# GPSClock.net
KiCad netlist of a schematic drawn in EAGLE
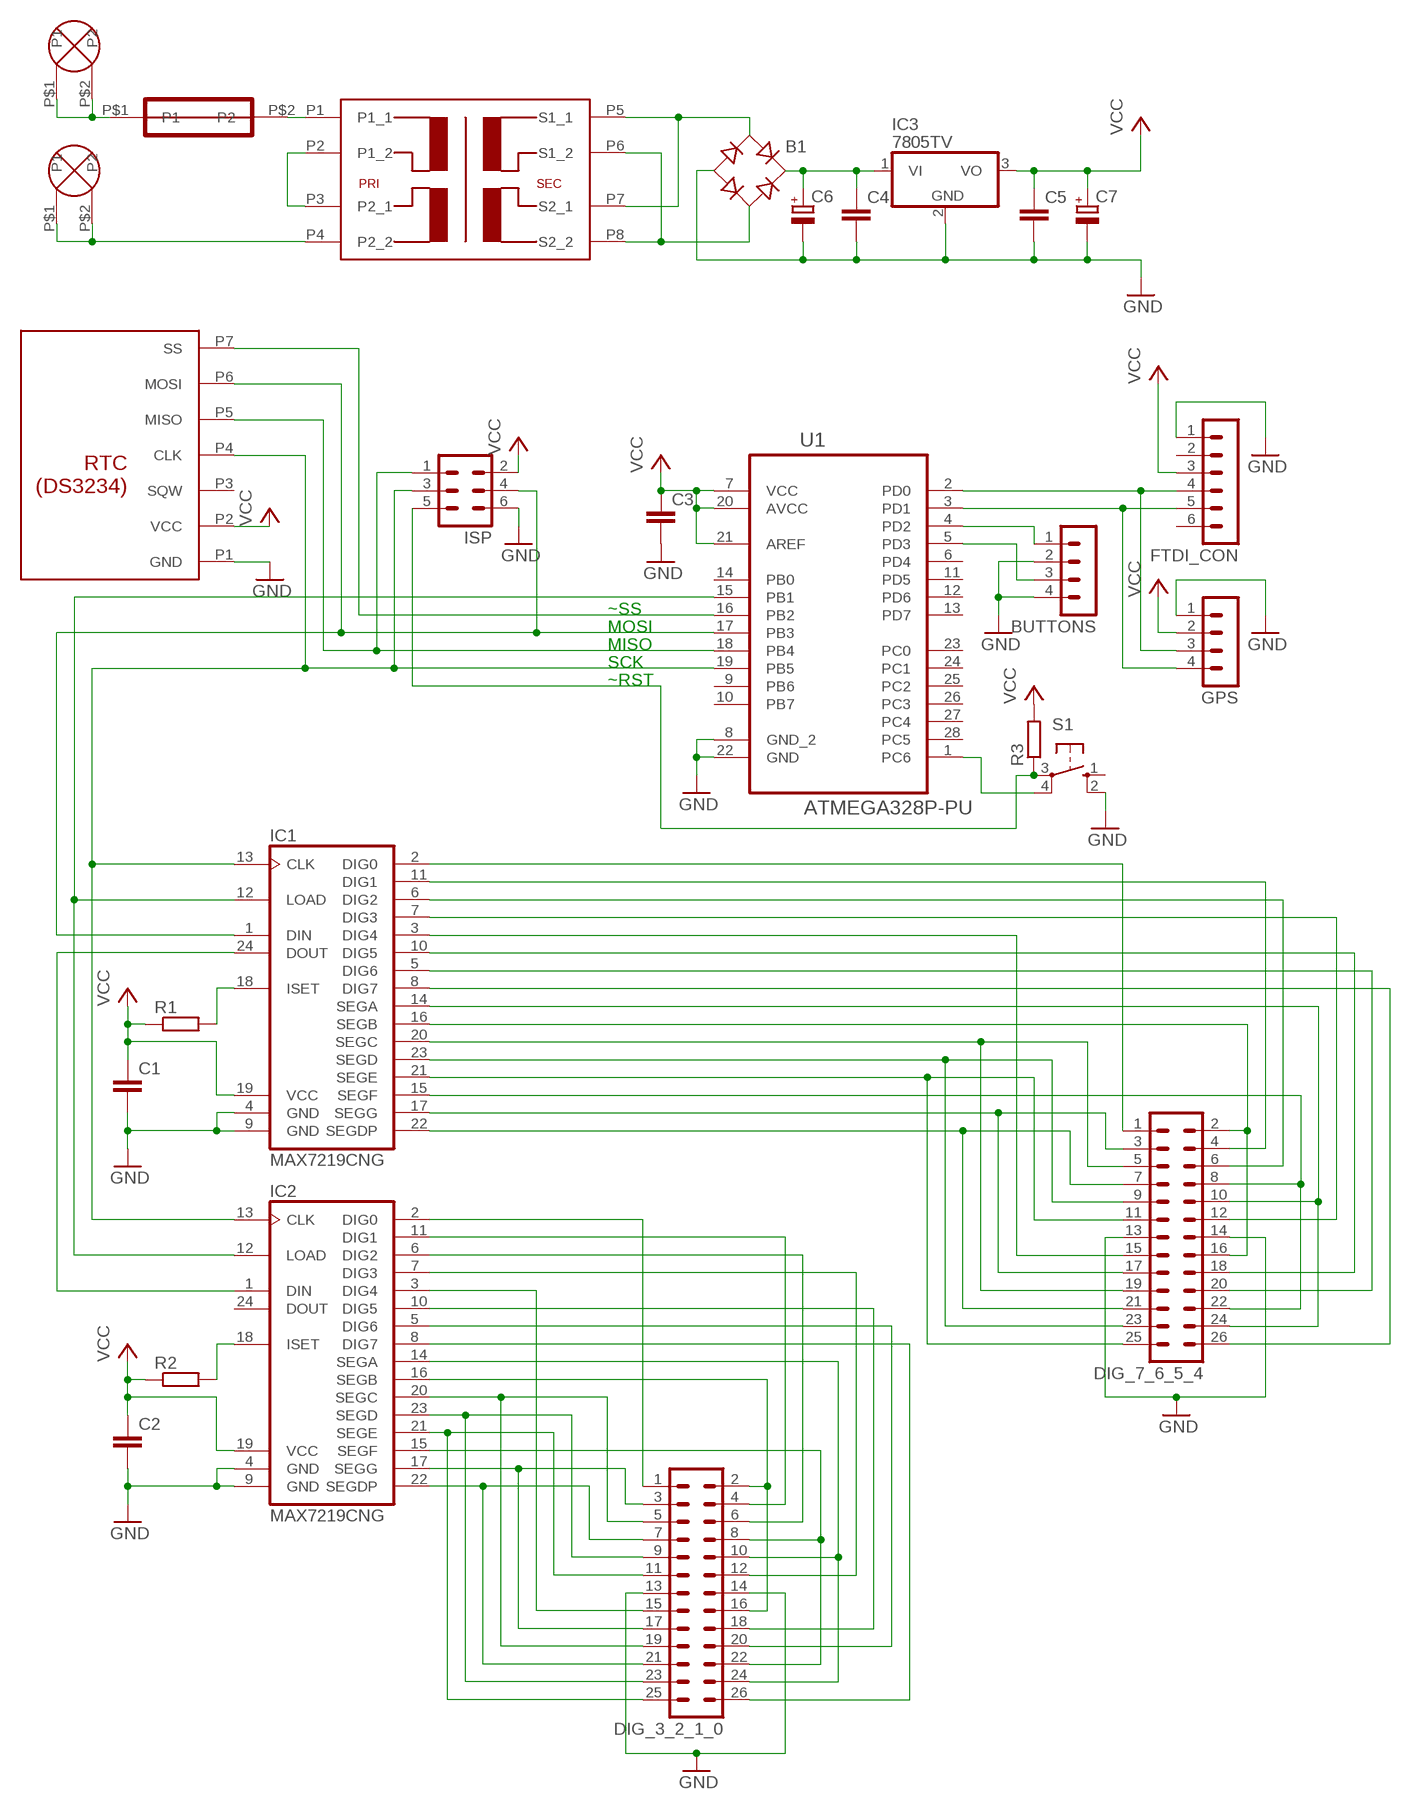
[diagram p0: schematic, sheet 1]

(export (version "E")
  (design (tool "Eeschema 10.0.6"))
  (components
    (comp (ref "B1")
      (value "RB1A")
      (footprint "eagle-import:RB1A")
      (libsource (lib "eagle-import") (part "RB1A"))
    )
    (comp (ref "BUTTONS")
      (value "MA04-1")
      (footprint "eagle-import:MA04-1")
      (libsource (lib "eagle-import") (part "MA04-1"))
    )
    (comp (ref "C1")
      (value "C-EU050-025X075")
      (footprint "eagle-import:C050-025X075")
      (libsource (lib "eagle-import") (part "C-EU050-025X075"))
    )
    (comp (ref "C2")
      (value "C-EU050-025X075")
      (footprint "eagle-import:C050-025X075")
      (libsource (lib "eagle-import") (part "C-EU050-025X075"))
    )
    (comp (ref "C3")
      (value "C-EU050-025X075")
      (footprint "eagle-import:C050-025X075")
      (libsource (lib "eagle-import") (part "C-EU050-025X075"))
    )
    (comp (ref "C4")
      (value "C-EU050-025X075")
      (footprint "eagle-import:C050-025X075")
      (libsource (lib "eagle-import") (part "C-EU050-025X075"))
    )
    (comp (ref "C5")
      (value "C-EU050-025X075")
      (footprint "eagle-import:C050-025X075")
      (libsource (lib "eagle-import") (part "C-EU050-025X075"))
    )
    (comp (ref "C6")
      (value "CPOL-EUE5-13")
      (footprint "eagle-import:E5-13")
      (libsource (lib "eagle-import") (part "CPOL-EUE5-13"))
    )
    (comp (ref "C7")
      (value "CPOL-EUE5-10.5")
      (footprint "eagle-import:E5-10,5")
      (libsource (lib "eagle-import") (part "CPOL-EUE5-10.5"))
    )
    (comp (ref "DIG_3_2_1_0")
      (value "ML26")
      (footprint "eagle-import:ML26")
      (libsource (lib "eagle-import") (part "ML26"))
    )
    (comp (ref "DIG_7_6_5_4")
      (value "ML26")
      (footprint "eagle-import:ML26")
      (libsource (lib "eagle-import") (part "ML26"))
    )
    (comp (ref "FTDI_CON")
      (value "MA06-1")
      (footprint "eagle-import:MA06-1")
      (libsource (lib "eagle-import") (part "MA06-1"))
    )
    (comp (ref "GPS")
      (value "MA04-1")
      (footprint "eagle-import:MA04-1")
      (libsource (lib "eagle-import") (part "MA04-1"))
    )
    (comp (ref "IC1")
      (value "MAX7219CNG")
      (footprint "eagle-import:DIL24-3")
      (fields (field (name "MF") "MAXIM"))
      (libsource (lib "eagle-import") (part "MAX7219CNG"))
    )
    (comp (ref "IC2")
      (value "MAX7219CNG")
      (footprint "eagle-import:DIL24-3")
      (fields (field (name "MF") "MAXIM"))
      (libsource (lib "eagle-import") (part "MAX7219CNG"))
    )
    (comp (ref "IC3")
      (value "7805TV")
      (footprint "eagle-import:TO220V")
      (libsource (lib "eagle-import") (part "78TV05"))
    )
    (comp (ref "ISP")
      (value "ML6")
      (footprint "eagle-import:ML6")
      (libsource (lib "eagle-import") (part "ML6"))
    )
    (comp (ref "R1")
      (value "R-EU_0207/10")
      (footprint "eagle-import:0207_10")
      (libsource (lib "eagle-import") (part "R-EU_0207/10"))
    )
    (comp (ref "R2")
      (value "R-EU_0207/10")
      (footprint "eagle-import:0207_10")
      (libsource (lib "eagle-import") (part "R-EU_0207/10"))
    )
    (comp (ref "R3")
      (value "R-EU_0207/10")
      (footprint "eagle-import:0207_10")
      (libsource (lib "eagle-import") (part "R-EU_0207/10"))
    )
    (comp (ref "S1")
      (value "10-XX")
      (footprint "eagle-import:B3F-10XX")
      (fields (field (name "MPN") "B3F-1000"))
      (libsource (lib "eagle-import") (part "10-XX"))
    )
    (comp (ref "U$1")
      (value "TRAFO_M4312")
      (footprint "eagle-import:TRAFO_M4312")
      (libsource (lib "eagle-import") (part "TRAFO_M4312"))
    )
    (comp (ref "U$2")
      (value "SPADE_PCB")
      (footprint "eagle-import:SPADE_PCB")
      (libsource (lib "eagle-import") (part "SPADE_PCB"))
    )
    (comp (ref "U$3")
      (value "SPADE_PCB")
      (footprint "eagle-import:SPADE_PCB")
      (libsource (lib "eagle-import") (part "SPADE_PCB"))
    )
    (comp (ref "U$4")
      (value "FUSE_HOLDER")
      (footprint "eagle-import:FUSE_HOLDER")
      (libsource (lib "eagle-import") (part "FUSE_HOLDER"))
    )
    (comp (ref "U$5")
      (value "RTC")
      (footprint "eagle-import:RTC")
      (libsource (lib "eagle-import") (part "RTC"))
    )
    (comp (ref "U1")
      (value "ATMEGA328P-PU")
      (footprint "eagle-import:DIP254P762X457-28")
      (libsource (lib "eagle-import") (part "ATMEGA328P-PU"))
    )
  )
  (nets
    (net (code "1") (name "GND") (class "Default")
      (node (ref "B1") (pin "-") (pinfunction "-_-") (pintype "passive"))
      (node (ref "BUTTONS") (pin "2") (pinfunction "2_2") (pintype "passive"))
      (node (ref "BUTTONS") (pin "4") (pinfunction "4_4") (pintype "passive"))
      (node (ref "C1") (pin "2") (pinfunction "2_2") (pintype "passive"))
      (node (ref "C2") (pin "2") (pinfunction "2_2") (pintype "passive"))
      (node (ref "C3") (pin "2") (pinfunction "2_2") (pintype "passive"))
      (node (ref "C4") (pin "2") (pinfunction "2_2") (pintype "passive"))
      (node (ref "C5") (pin "2") (pinfunction "2_2") (pintype "passive"))
      (node (ref "C6") (pin "-") (pinfunction "-_-") (pintype "passive"))
      (node (ref "C7") (pin "-") (pinfunction "-_-") (pintype "passive"))
      (node (ref "DIG_3_2_1_0") (pin "13") (pinfunction "13_13") (pintype "passive"))
      (node (ref "DIG_3_2_1_0") (pin "14") (pinfunction "14_14") (pintype "passive"))
      (node (ref "DIG_7_6_5_4") (pin "13") (pinfunction "13_13") (pintype "passive"))
      (node (ref "DIG_7_6_5_4") (pin "14") (pinfunction "14_14") (pintype "passive"))
      (node (ref "FTDI_CON") (pin "1") (pinfunction "1_1") (pintype "passive"))
      (node (ref "GPS") (pin "1") (pinfunction "1_1") (pintype "passive"))
      (node (ref "IC1") (pin "4") (pinfunction "GND_4") (pintype "power_in"))
      (node (ref "IC1") (pin "9") (pinfunction "GND_9") (pintype "power_in"))
      (node (ref "IC2") (pin "4") (pinfunction "GND_4") (pintype "power_in"))
      (node (ref "IC2") (pin "9") (pinfunction "GND_9") (pintype "power_in"))
      (node (ref "IC3") (pin "2") (pinfunction "GND_2") (pintype "passive"))
      (node (ref "ISP") (pin "6") (pinfunction "6_6") (pintype "passive"))
      (node (ref "S1") (pin "2") (pinfunction "S1_2") (pintype "passive"))
      (node (ref "U$5") (pin "P1") (pinfunction "GND_P1") (pintype "bidirectional"))
      (node (ref "U1") (pin "22") (pinfunction "GND_22") (pintype "passive"))
      (node (ref "U1") (pin "8") (pinfunction "GND_2_8") (pintype "passive"))
    )
    (net (code "2") (name "Net-(IC1-CLK)") (class "Default")
      (node (ref "IC1") (pin "13") (pinfunction "CLK_13") (pintype "input"))
      (node (ref "IC2") (pin "13") (pinfunction "CLK_13") (pintype "input"))
      (node (ref "ISP") (pin "3") (pinfunction "3_3") (pintype "passive"))
      (node (ref "U$5") (pin "P4") (pinfunction "CLK_P4") (pintype "bidirectional"))
      (node (ref "U1") (pin "19") (pinfunction "PB5_19") (pintype "bidirectional"))
    )
    (net (code "3") (name "Net-(IC1-DIG0)") (class "Default")
      (node (ref "DIG_7_6_5_4") (pin "1") (pinfunction "1_1") (pintype "passive"))
      (node (ref "IC1") (pin "2") (pinfunction "DIG0_2") (pintype "output"))
    )
    (net (code "4") (name "Net-(IC1-DIG1)") (class "Default")
      (node (ref "DIG_7_6_5_4") (pin "4") (pinfunction "4_4") (pintype "passive"))
      (node (ref "IC1") (pin "11") (pinfunction "DIG1_11") (pintype "output"))
    )
    (net (code "5") (name "Net-(IC1-DIG2)") (class "Default")
      (node (ref "DIG_7_6_5_4") (pin "6") (pinfunction "6_6") (pintype "passive"))
      (node (ref "IC1") (pin "6") (pinfunction "DIG2_6") (pintype "output"))
    )
    (net (code "6") (name "Net-(IC1-DIG3)") (class "Default")
      (node (ref "DIG_7_6_5_4") (pin "12") (pinfunction "12_12") (pintype "passive"))
      (node (ref "IC1") (pin "7") (pinfunction "DIG3_7") (pintype "output"))
    )
    (net (code "7") (name "Net-(IC1-DIG4)") (class "Default")
      (node (ref "DIG_7_6_5_4") (pin "15") (pinfunction "15_15") (pintype "passive"))
      (node (ref "IC1") (pin "3") (pinfunction "DIG4_3") (pintype "output"))
    )
    (net (code "8") (name "Net-(IC1-DIG5)") (class "Default")
      (node (ref "DIG_7_6_5_4") (pin "18") (pinfunction "18_18") (pintype "passive"))
      (node (ref "IC1") (pin "10") (pinfunction "DIG5_10") (pintype "output"))
    )
    (net (code "9") (name "Net-(IC1-DIG6)") (class "Default")
      (node (ref "DIG_7_6_5_4") (pin "20") (pinfunction "20_20") (pintype "passive"))
      (node (ref "IC1") (pin "5") (pinfunction "DIG6_5") (pintype "output"))
    )
    (net (code "10") (name "Net-(IC1-DIG7)") (class "Default")
      (node (ref "DIG_7_6_5_4") (pin "26") (pinfunction "26_26") (pintype "passive"))
      (node (ref "IC1") (pin "8") (pinfunction "DIG7_8") (pintype "output"))
    )
    (net (code "11") (name "Net-(IC1-DIN)") (class "Default")
      (node (ref "IC1") (pin "1") (pinfunction "DIN_1") (pintype "input"))
      (node (ref "ISP") (pin "4") (pinfunction "4_4") (pintype "passive"))
      (node (ref "U$5") (pin "P6") (pinfunction "MOSI_P6") (pintype "bidirectional"))
      (node (ref "U1") (pin "17") (pinfunction "PB3_17") (pintype "bidirectional"))
    )
    (net (code "12") (name "Net-(IC1-DOUT)") (class "Default")
      (node (ref "IC1") (pin "24") (pinfunction "DOUT_24") (pintype "output"))
      (node (ref "IC2") (pin "1") (pinfunction "DIN_1") (pintype "input"))
    )
    (net (code "13") (name "Net-(IC1-ISET)") (class "Default")
      (node (ref "IC1") (pin "18") (pinfunction "ISET_18") (pintype "input"))
      (node (ref "R1") (pin "2") (pinfunction "2_2") (pintype "passive"))
    )
    (net (code "14") (name "Net-(IC1-LOAD)") (class "Default")
      (node (ref "IC1") (pin "12") (pinfunction "LOAD_12") (pintype "input"))
      (node (ref "IC2") (pin "12") (pinfunction "LOAD_12") (pintype "input"))
      (node (ref "U1") (pin "15") (pinfunction "PB1_15") (pintype "bidirectional"))
    )
    (net (code "15") (name "Net-(IC1-SEGA)") (class "Default")
      (node (ref "DIG_7_6_5_4") (pin "10") (pinfunction "10_10") (pintype "passive"))
      (node (ref "DIG_7_6_5_4") (pin "24") (pinfunction "24_24") (pintype "passive"))
      (node (ref "IC1") (pin "14") (pinfunction "SEGA_14") (pintype "output"))
    )
    (net (code "16") (name "Net-(IC1-SEGB)") (class "Default")
      (node (ref "DIG_7_6_5_4") (pin "16") (pinfunction "16_16") (pintype "passive"))
      (node (ref "DIG_7_6_5_4") (pin "2") (pinfunction "2_2") (pintype "passive"))
      (node (ref "IC1") (pin "16") (pinfunction "SEGB_16") (pintype "output"))
    )
    (net (code "17") (name "Net-(IC1-SEGC)") (class "Default")
      (node (ref "DIG_7_6_5_4") (pin "19") (pinfunction "19_19") (pintype "passive"))
      (node (ref "DIG_7_6_5_4") (pin "5") (pinfunction "5_5") (pintype "passive"))
      (node (ref "IC1") (pin "20") (pinfunction "SEGC_20") (pintype "output"))
    )
    (net (code "18") (name "Net-(IC1-SEGD)") (class "Default")
      (node (ref "DIG_7_6_5_4") (pin "23") (pinfunction "23_23") (pintype "passive"))
      (node (ref "DIG_7_6_5_4") (pin "9") (pinfunction "9_9") (pintype "passive"))
      (node (ref "IC1") (pin "23") (pinfunction "SEGD_23") (pintype "output"))
    )
    (net (code "19") (name "Net-(IC1-SEGDP)") (class "Default")
      (node (ref "DIG_7_6_5_4") (pin "21") (pinfunction "21_21") (pintype "passive"))
      (node (ref "DIG_7_6_5_4") (pin "7") (pinfunction "7_7") (pintype "passive"))
      (node (ref "IC1") (pin "22") (pinfunction "SEGDP_22") (pintype "output"))
    )
    (net (code "20") (name "Net-(IC1-SEGE)") (class "Default")
      (node (ref "DIG_7_6_5_4") (pin "11") (pinfunction "11_11") (pintype "passive"))
      (node (ref "DIG_7_6_5_4") (pin "25") (pinfunction "25_25") (pintype "passive"))
      (node (ref "IC1") (pin "21") (pinfunction "SEGE_21") (pintype "output"))
    )
    (net (code "21") (name "Net-(IC1-SEGF)") (class "Default")
      (node (ref "DIG_7_6_5_4") (pin "22") (pinfunction "22_22") (pintype "passive"))
      (node (ref "DIG_7_6_5_4") (pin "8") (pinfunction "8_8") (pintype "passive"))
      (node (ref "IC1") (pin "15") (pinfunction "SEGF_15") (pintype "output"))
    )
    (net (code "22") (name "Net-(IC1-SEGG)") (class "Default")
      (node (ref "DIG_7_6_5_4") (pin "17") (pinfunction "17_17") (pintype "passive"))
      (node (ref "DIG_7_6_5_4") (pin "3") (pinfunction "3_3") (pintype "passive"))
      (node (ref "IC1") (pin "17") (pinfunction "SEGG_17") (pintype "output"))
    )
    (net (code "23") (name "Net-(IC2-DIG0)") (class "Default")
      (node (ref "DIG_3_2_1_0") (pin "1") (pinfunction "1_1") (pintype "passive"))
      (node (ref "IC2") (pin "2") (pinfunction "DIG0_2") (pintype "output"))
    )
    (net (code "24") (name "Net-(IC2-DIG1)") (class "Default")
      (node (ref "DIG_3_2_1_0") (pin "4") (pinfunction "4_4") (pintype "passive"))
      (node (ref "IC2") (pin "11") (pinfunction "DIG1_11") (pintype "output"))
    )
    (net (code "25") (name "Net-(IC2-DIG2)") (class "Default")
      (node (ref "DIG_3_2_1_0") (pin "6") (pinfunction "6_6") (pintype "passive"))
      (node (ref "IC2") (pin "6") (pinfunction "DIG2_6") (pintype "output"))
    )
    (net (code "26") (name "Net-(IC2-DIG3)") (class "Default")
      (node (ref "DIG_3_2_1_0") (pin "12") (pinfunction "12_12") (pintype "passive"))
      (node (ref "IC2") (pin "7") (pinfunction "DIG3_7") (pintype "output"))
    )
    (net (code "27") (name "Net-(IC2-DIG4)") (class "Default")
      (node (ref "DIG_3_2_1_0") (pin "15") (pinfunction "15_15") (pintype "passive"))
      (node (ref "IC2") (pin "3") (pinfunction "DIG4_3") (pintype "output"))
    )
    (net (code "28") (name "Net-(IC2-DIG5)") (class "Default")
      (node (ref "DIG_3_2_1_0") (pin "18") (pinfunction "18_18") (pintype "passive"))
      (node (ref "IC2") (pin "10") (pinfunction "DIG5_10") (pintype "output"))
    )
    (net (code "29") (name "Net-(IC2-DIG6)") (class "Default")
      (node (ref "DIG_3_2_1_0") (pin "20") (pinfunction "20_20") (pintype "passive"))
      (node (ref "IC2") (pin "5") (pinfunction "DIG6_5") (pintype "output"))
    )
    (net (code "30") (name "Net-(IC2-DIG7)") (class "Default")
      (node (ref "DIG_3_2_1_0") (pin "26") (pinfunction "26_26") (pintype "passive"))
      (node (ref "IC2") (pin "8") (pinfunction "DIG7_8") (pintype "output"))
    )
    (net (code "31") (name "Net-(IC2-ISET)") (class "Default")
      (node (ref "IC2") (pin "18") (pinfunction "ISET_18") (pintype "input"))
      (node (ref "R2") (pin "2") (pinfunction "2_2") (pintype "passive"))
    )
    (net (code "32") (name "Net-(IC2-SEGA)") (class "Default")
      (node (ref "DIG_3_2_1_0") (pin "10") (pinfunction "10_10") (pintype "passive"))
      (node (ref "DIG_3_2_1_0") (pin "24") (pinfunction "24_24") (pintype "passive"))
      (node (ref "IC2") (pin "14") (pinfunction "SEGA_14") (pintype "output"))
    )
    (net (code "33") (name "Net-(IC2-SEGB)") (class "Default")
      (node (ref "DIG_3_2_1_0") (pin "16") (pinfunction "16_16") (pintype "passive"))
      (node (ref "DIG_3_2_1_0") (pin "2") (pinfunction "2_2") (pintype "passive"))
      (node (ref "IC2") (pin "16") (pinfunction "SEGB_16") (pintype "output"))
    )
    (net (code "34") (name "Net-(IC2-SEGC)") (class "Default")
      (node (ref "DIG_3_2_1_0") (pin "19") (pinfunction "19_19") (pintype "passive"))
      (node (ref "DIG_3_2_1_0") (pin "5") (pinfunction "5_5") (pintype "passive"))
      (node (ref "IC2") (pin "20") (pinfunction "SEGC_20") (pintype "output"))
    )
    (net (code "35") (name "Net-(IC2-SEGD)") (class "Default")
      (node (ref "DIG_3_2_1_0") (pin "23") (pinfunction "23_23") (pintype "passive"))
      (node (ref "DIG_3_2_1_0") (pin "9") (pinfunction "9_9") (pintype "passive"))
      (node (ref "IC2") (pin "23") (pinfunction "SEGD_23") (pintype "output"))
    )
    (net (code "36") (name "Net-(IC2-SEGDP)") (class "Default")
      (node (ref "DIG_3_2_1_0") (pin "21") (pinfunction "21_21") (pintype "passive"))
      (node (ref "DIG_3_2_1_0") (pin "7") (pinfunction "7_7") (pintype "passive"))
      (node (ref "IC2") (pin "22") (pinfunction "SEGDP_22") (pintype "output"))
    )
    (net (code "37") (name "Net-(IC2-SEGE)") (class "Default")
      (node (ref "DIG_3_2_1_0") (pin "11") (pinfunction "11_11") (pintype "passive"))
      (node (ref "DIG_3_2_1_0") (pin "25") (pinfunction "25_25") (pintype "passive"))
      (node (ref "IC2") (pin "21") (pinfunction "SEGE_21") (pintype "output"))
    )
    (net (code "38") (name "Net-(IC2-SEGF)") (class "Default")
      (node (ref "DIG_3_2_1_0") (pin "22") (pinfunction "22_22") (pintype "passive"))
      (node (ref "DIG_3_2_1_0") (pin "8") (pinfunction "8_8") (pintype "passive"))
      (node (ref "IC2") (pin "15") (pinfunction "SEGF_15") (pintype "output"))
    )
    (net (code "39") (name "Net-(IC2-SEGG)") (class "Default")
      (node (ref "DIG_3_2_1_0") (pin "17") (pinfunction "17_17") (pintype "passive"))
      (node (ref "DIG_3_2_1_0") (pin "3") (pinfunction "3_3") (pintype "passive"))
      (node (ref "IC2") (pin "17") (pinfunction "SEGG_17") (pintype "output"))
    )
    (net (code "40") (name "Net-(IC3-VI)") (class "Default")
      (node (ref "B1") (pin "+") (pinfunction "+_+") (pintype "passive"))
      (node (ref "C4") (pin "1") (pinfunction "1_1") (pintype "passive"))
      (node (ref "C6") (pin "+") (pinfunction "+_+") (pintype "passive"))
      (node (ref "IC3") (pin "1") (pinfunction "VI_1") (pintype "input"))
    )
    (net (code "41") (name "Net-(S1-P)") (class "Default")
      (node (ref "ISP") (pin "5") (pinfunction "5_5") (pintype "passive"))
      (node (ref "R3") (pin "1") (pinfunction "1_1") (pintype "passive"))
      (node (ref "S1") (pin "3") (pinfunction "P_3") (pintype "passive"))
    )
    (net (code "42") (name "Net-(S1-P1)") (class "Default")
      (node (ref "S1") (pin "4") (pinfunction "P1_4") (pintype "passive"))
      (node (ref "U1") (pin "1") (pinfunction "PC6_1") (pintype "bidirectional"))
    )
    (net (code "43") (name "Net-(U$1-P1_1)") (class "Default")
      (node (ref "U$1") (pin "P1") (pinfunction "P1_1_P1") (pintype "bidirectional"))
      (node (ref "U$4") (pin "P$2") (pinfunction "P2_P$2") (pintype "bidirectional"))
    )
    (net (code "44") (name "Net-(U$1-P1_2)") (class "Default")
      (node (ref "U$1") (pin "P2") (pinfunction "P1_2_P2") (pintype "bidirectional"))
      (node (ref "U$1") (pin "P3") (pinfunction "P2_1_P3") (pintype "bidirectional"))
    )
    (net (code "45") (name "Net-(U$1-P2_2)") (class "Default")
      (node (ref "U$1") (pin "P4") (pinfunction "P2_2_P4") (pintype "bidirectional"))
      (node (ref "U$2") (pin "P$1") (pinfunction "P1_P$1") (pintype "bidirectional"))
      (node (ref "U$2") (pin "P$2") (pinfunction "P2_P$2") (pintype "bidirectional"))
    )
    (net (code "46") (name "Net-(U$1-S1_1)") (class "Default")
      (node (ref "B1") (pin "AC1") (pinfunction "AC1_AC1") (pintype "passive"))
      (node (ref "U$1") (pin "P5") (pinfunction "S1_1_P5") (pintype "bidirectional"))
      (node (ref "U$1") (pin "P7") (pinfunction "S2_1_P7") (pintype "bidirectional"))
    )
    (net (code "47") (name "Net-(U$1-S1_2)") (class "Default")
      (node (ref "B1") (pin "AC2") (pinfunction "AC2_AC2") (pintype "passive"))
      (node (ref "U$1") (pin "P6") (pinfunction "S1_2_P6") (pintype "bidirectional"))
      (node (ref "U$1") (pin "P8") (pinfunction "S2_2_P8") (pintype "bidirectional"))
    )
    (net (code "48") (name "Net-(U$3-P1)") (class "Default")
      (node (ref "U$3") (pin "P$1") (pinfunction "P1_P$1") (pintype "bidirectional"))
      (node (ref "U$3") (pin "P$2") (pinfunction "P2_P$2") (pintype "bidirectional"))
      (node (ref "U$4") (pin "P$1") (pinfunction "P1_P$1") (pintype "bidirectional"))
    )
    (net (code "49") (name "Net-(U$5-MISO)") (class "Default")
      (node (ref "ISP") (pin "1") (pinfunction "1_1") (pintype "passive"))
      (node (ref "U$5") (pin "P5") (pinfunction "MISO_P5") (pintype "bidirectional"))
      (node (ref "U1") (pin "18") (pinfunction "PB4_18") (pintype "bidirectional"))
    )
    (net (code "50") (name "Net-(U$5-SS)") (class "Default")
      (node (ref "U$5") (pin "P7") (pinfunction "SS_P7") (pintype "bidirectional"))
      (node (ref "U1") (pin "16") (pinfunction "PB2_16") (pintype "bidirectional"))
    )
    (net (code "51") (name "Net-(U1-PD0)") (class "Default")
      (node (ref "FTDI_CON") (pin "4") (pinfunction "4_4") (pintype "passive"))
      (node (ref "GPS") (pin "3") (pinfunction "3_3") (pintype "passive"))
      (node (ref "U1") (pin "2") (pinfunction "PD0_2") (pintype "bidirectional"))
    )
    (net (code "52") (name "Net-(U1-PD1)") (class "Default")
      (node (ref "FTDI_CON") (pin "5") (pinfunction "5_5") (pintype "passive"))
      (node (ref "GPS") (pin "4") (pinfunction "4_4") (pintype "passive"))
      (node (ref "U1") (pin "3") (pinfunction "PD1_3") (pintype "bidirectional"))
    )
    (net (code "53") (name "Net-(U1-PD2)") (class "Default")
      (node (ref "BUTTONS") (pin "1") (pinfunction "1_1") (pintype "passive"))
      (node (ref "U1") (pin "4") (pinfunction "PD2_4") (pintype "bidirectional"))
    )
    (net (code "54") (name "Net-(U1-PD3)") (class "Default")
      (node (ref "BUTTONS") (pin "3") (pinfunction "3_3") (pintype "passive"))
      (node (ref "U1") (pin "5") (pinfunction "PD3_5") (pintype "bidirectional"))
    )
    (net (code "55") (name "VCC") (class "Default")
      (node (ref "C1") (pin "1") (pinfunction "1_1") (pintype "passive"))
      (node (ref "C2") (pin "1") (pinfunction "1_1") (pintype "passive"))
      (node (ref "C3") (pin "1") (pinfunction "1_1") (pintype "passive"))
      (node (ref "C5") (pin "1") (pinfunction "1_1") (pintype "passive"))
      (node (ref "C7") (pin "+") (pinfunction "+_+") (pintype "passive"))
      (node (ref "FTDI_CON") (pin "3") (pinfunction "3_3") (pintype "passive"))
      (node (ref "GPS") (pin "2") (pinfunction "2_2") (pintype "passive"))
      (node (ref "IC1") (pin "19") (pinfunction "VCC_19") (pintype "power_in"))
      (node (ref "IC2") (pin "19") (pinfunction "VCC_19") (pintype "power_in"))
      (node (ref "IC3") (pin "3") (pinfunction "VO_3") (pintype "passive"))
      (node (ref "ISP") (pin "2") (pinfunction "2_2") (pintype "passive"))
      (node (ref "R1") (pin "1") (pinfunction "1_1") (pintype "passive"))
      (node (ref "R2") (pin "1") (pinfunction "1_1") (pintype "passive"))
      (node (ref "R3") (pin "2") (pinfunction "2_2") (pintype "passive"))
      (node (ref "U$5") (pin "P2") (pinfunction "VCC_P2") (pintype "bidirectional"))
      (node (ref "U1") (pin "20") (pinfunction "AVCC_20") (pintype "power_in"))
      (node (ref "U1") (pin "21") (pinfunction "AREF_21") (pintype "input"))
      (node (ref "U1") (pin "7") (pinfunction "VCC_7") (pintype "power_in"))
    )
    (net (code "56") (name "unconnected-(FTDI_CON-Pad2)") (class "Default")
      (node (ref "FTDI_CON") (pin "2") (pinfunction "2_2") (pintype "passive"))
    )
    (net (code "57") (name "unconnected-(FTDI_CON-Pad6)") (class "Default")
      (node (ref "FTDI_CON") (pin "6") (pinfunction "6_6") (pintype "passive"))
    )
    (net (code "58") (name "unconnected-(IC2-DOUT-Pad24)") (class "Default")
      (node (ref "IC2") (pin "24") (pinfunction "DOUT_24") (pintype "output"))
    )
    (net (code "59") (name "unconnected-(S1-S-Pad1)") (class "Default")
      (node (ref "S1") (pin "1") (pinfunction "S_1") (pintype "passive"))
    )
    (net (code "60") (name "unconnected-(U$5-SQW-PadP3)") (class "Default")
      (node (ref "U$5") (pin "P3") (pinfunction "SQW_P3") (pintype "bidirectional"))
    )
    (net (code "61") (name "unconnected-(U1-PB0-Pad14)") (class "Default")
      (node (ref "U1") (pin "14") (pinfunction "PB0_14") (pintype "bidirectional"))
    )
    (net (code "62") (name "unconnected-(U1-PB6-Pad9)") (class "Default")
      (node (ref "U1") (pin "9") (pinfunction "PB6_9") (pintype "bidirectional"))
    )
    (net (code "63") (name "unconnected-(U1-PB7-Pad10)") (class "Default")
      (node (ref "U1") (pin "10") (pinfunction "PB7_10") (pintype "bidirectional"))
    )
    (net (code "64") (name "unconnected-(U1-PC0-Pad23)") (class "Default")
      (node (ref "U1") (pin "23") (pinfunction "PC0_23") (pintype "bidirectional"))
    )
    (net (code "65") (name "unconnected-(U1-PC1-Pad24)") (class "Default")
      (node (ref "U1") (pin "24") (pinfunction "PC1_24") (pintype "bidirectional"))
    )
    (net (code "66") (name "unconnected-(U1-PC2-Pad25)") (class "Default")
      (node (ref "U1") (pin "25") (pinfunction "PC2_25") (pintype "bidirectional"))
    )
    (net (code "67") (name "unconnected-(U1-PC3-Pad26)") (class "Default")
      (node (ref "U1") (pin "26") (pinfunction "PC3_26") (pintype "bidirectional"))
    )
    (net (code "68") (name "unconnected-(U1-PC4-Pad27)") (class "Default")
      (node (ref "U1") (pin "27") (pinfunction "PC4_27") (pintype "bidirectional"))
    )
    (net (code "69") (name "unconnected-(U1-PC5-Pad28)") (class "Default")
      (node (ref "U1") (pin "28") (pinfunction "PC5_28") (pintype "bidirectional"))
    )
    (net (code "70") (name "unconnected-(U1-PD4-Pad6)") (class "Default")
      (node (ref "U1") (pin "6") (pinfunction "PD4_6") (pintype "bidirectional"))
    )
    (net (code "71") (name "unconnected-(U1-PD5-Pad11)") (class "Default")
      (node (ref "U1") (pin "11") (pinfunction "PD5_11") (pintype "bidirectional"))
    )
    (net (code "72") (name "unconnected-(U1-PD6-Pad12)") (class "Default")
      (node (ref "U1") (pin "12") (pinfunction "PD6_12") (pintype "bidirectional"))
    )
    (net (code "73") (name "unconnected-(U1-PD7-Pad13)") (class "Default")
      (node (ref "U1") (pin "13") (pinfunction "PD7_13") (pintype "bidirectional"))
    )
  )
)
